# 0_CONNECTOR.net
KiCad netlist of a schematic drawn in Altium Designer
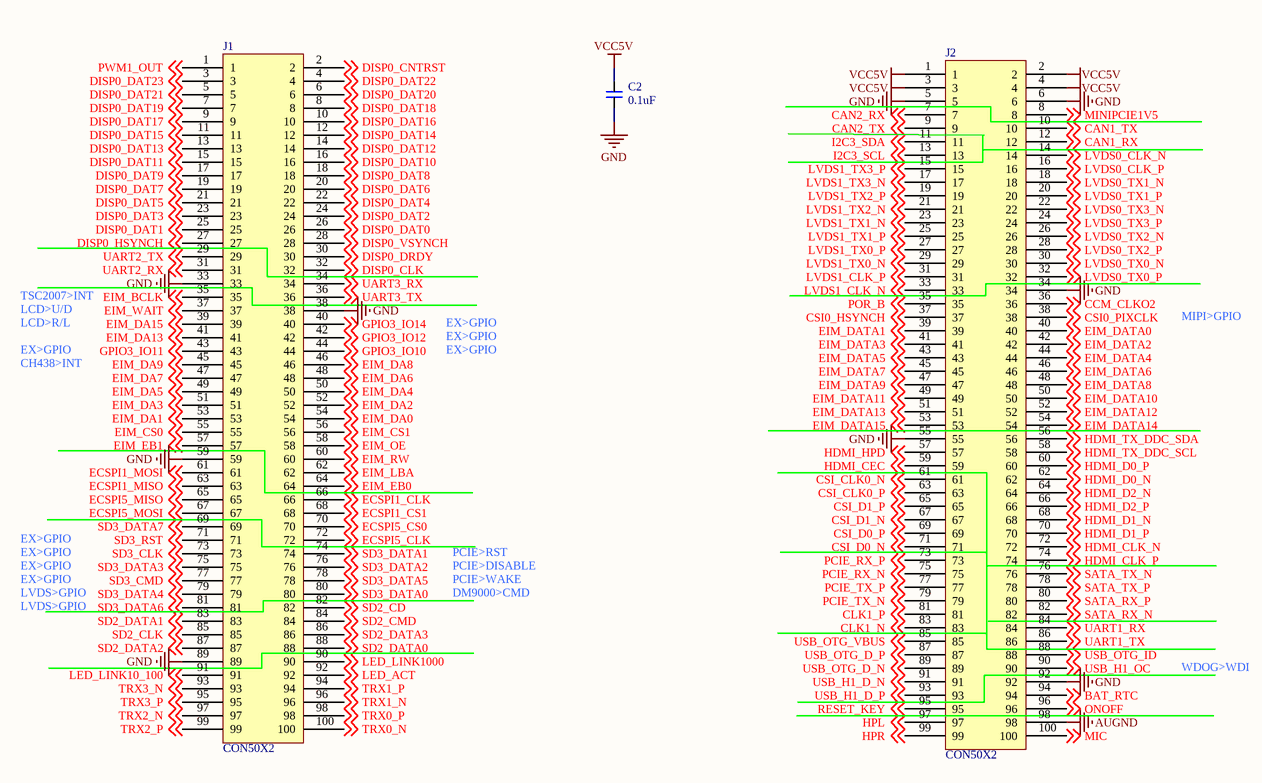
[diagram p0: 0.CONNECTOR.SchDoc]

(export (version "E")
  (design (tool "Eeschema 10.0.6"))
  (components
    (comp (ref "C2")
      (value "0.1uF")
      (footprint "0603C")
      (description "电容")
      (libsource (lib "LDT-SCH") (part "电容"))
    )
    (comp (ref "J1")
      (value "CON50X2")
      (footprint "IDC50X2-1.27MM_SMT")
      (description "ASTRON B2B Connector")
      (libsource (lib "LDT-SCH") (part "CON50X2"))
    )
    (comp (ref "J2")
      (value "CON50X2")
      (footprint "IDC50X2-1.27MM_SMT")
      (description "ASTRON B2B Connector")
      (libsource (lib "LDT-SCH") (part "CON50X2"))
    )
  )
  (nets
    (net (code "1") (name "AUGND") (class "Default")
      (node (ref "J2") (pin "98") (pinfunction "98_98") (pintype "passive"))
    )
    (net (code "2") (name "BAT_RTC") (class "Default")
      (node (ref "J2") (pin "94") (pinfunction "94_94") (pintype "passive"))
    )
    (net (code "3") (name "CAN1_RX") (class "Default")
      (node (ref "J2") (pin "12") (pinfunction "12_12") (pintype "passive"))
    )
    (net (code "4") (name "CAN1_TX") (class "Default")
      (node (ref "J2") (pin "10") (pinfunction "10_10") (pintype "passive"))
    )
    (net (code "5") (name "CAN2_RX") (class "Default")
      (node (ref "J2") (pin "7") (pinfunction "7_7") (pintype "passive"))
    )
    (net (code "6") (name "CAN2_TX") (class "Default")
      (node (ref "J2") (pin "9") (pinfunction "9_9") (pintype "passive"))
    )
    (net (code "7") (name "CCM_CLKO2") (class "Default")
      (node (ref "J2") (pin "36") (pinfunction "36_36") (pintype "passive"))
    )
    (net (code "8") (name "CLK1_N") (class "Default")
      (node (ref "J2") (pin "83") (pinfunction "83_83") (pintype "passive"))
    )
    (net (code "9") (name "CLK1_P") (class "Default")
      (node (ref "J2") (pin "81") (pinfunction "81_81") (pintype "passive"))
    )
    (net (code "10") (name "CSI0_HSYNCH") (class "Default")
      (node (ref "J2") (pin "37") (pinfunction "37_37") (pintype "passive"))
    )
    (net (code "11") (name "CSI0_PIXCLK") (class "Default")
      (node (ref "J2") (pin "38") (pinfunction "38_38") (pintype "passive"))
    )
    (net (code "12") (name "CSI_CLK0_N") (class "Default")
      (node (ref "J2") (pin "61") (pinfunction "61_61") (pintype "passive"))
    )
    (net (code "13") (name "CSI_CLK0_P") (class "Default")
      (node (ref "J2") (pin "63") (pinfunction "63_63") (pintype "passive"))
    )
    (net (code "14") (name "CSI_D0_N") (class "Default")
      (node (ref "J2") (pin "71") (pinfunction "71_71") (pintype "passive"))
    )
    (net (code "15") (name "CSI_D0_P") (class "Default")
      (node (ref "J2") (pin "69") (pinfunction "69_69") (pintype "passive"))
    )
    (net (code "16") (name "CSI_D1_N") (class "Default")
      (node (ref "J2") (pin "67") (pinfunction "67_67") (pintype "passive"))
    )
    (net (code "17") (name "CSI_D1_P") (class "Default")
      (node (ref "J2") (pin "65") (pinfunction "65_65") (pintype "passive"))
    )
    (net (code "18") (name "DISP0_CLK") (class "Default")
      (node (ref "J1") (pin "32") (pinfunction "32_32") (pintype "passive"))
    )
    (net (code "19") (name "DISP0_CNTRST") (class "Default")
      (node (ref "J1") (pin "2") (pinfunction "2_2") (pintype "passive"))
    )
    (net (code "20") (name "DISP0_DAT0") (class "Default")
      (node (ref "J1") (pin "26") (pinfunction "26_26") (pintype "passive"))
    )
    (net (code "21") (name "DISP0_DAT1") (class "Default")
      (node (ref "J1") (pin "25") (pinfunction "25_25") (pintype "passive"))
    )
    (net (code "22") (name "DISP0_DAT2") (class "Default")
      (node (ref "J1") (pin "24") (pinfunction "24_24") (pintype "passive"))
    )
    (net (code "23") (name "DISP0_DAT3") (class "Default")
      (node (ref "J1") (pin "23") (pinfunction "23_23") (pintype "passive"))
    )
    (net (code "24") (name "DISP0_DAT4") (class "Default")
      (node (ref "J1") (pin "22") (pinfunction "22_22") (pintype "passive"))
    )
    (net (code "25") (name "DISP0_DAT5") (class "Default")
      (node (ref "J1") (pin "21") (pinfunction "21_21") (pintype "passive"))
    )
    (net (code "26") (name "DISP0_DAT6") (class "Default")
      (node (ref "J1") (pin "20") (pinfunction "20_20") (pintype "passive"))
    )
    (net (code "27") (name "DISP0_DAT7") (class "Default")
      (node (ref "J1") (pin "19") (pinfunction "19_19") (pintype "passive"))
    )
    (net (code "28") (name "DISP0_DAT8") (class "Default")
      (node (ref "J1") (pin "18") (pinfunction "18_18") (pintype "passive"))
    )
    (net (code "29") (name "DISP0_DAT9") (class "Default")
      (node (ref "J1") (pin "17") (pinfunction "17_17") (pintype "passive"))
    )
    (net (code "30") (name "DISP0_DAT10") (class "Default")
      (node (ref "J1") (pin "16") (pinfunction "16_16") (pintype "passive"))
    )
    (net (code "31") (name "DISP0_DAT11") (class "Default")
      (node (ref "J1") (pin "15") (pinfunction "15_15") (pintype "passive"))
    )
    (net (code "32") (name "DISP0_DAT12") (class "Default")
      (node (ref "J1") (pin "14") (pinfunction "14_14") (pintype "passive"))
    )
    (net (code "33") (name "DISP0_DAT13") (class "Default")
      (node (ref "J1") (pin "13") (pinfunction "13_13") (pintype "passive"))
    )
    (net (code "34") (name "DISP0_DAT14") (class "Default")
      (node (ref "J1") (pin "12") (pinfunction "12_12") (pintype "passive"))
    )
    (net (code "35") (name "DISP0_DAT15") (class "Default")
      (node (ref "J1") (pin "11") (pinfunction "11_11") (pintype "passive"))
    )
    (net (code "36") (name "DISP0_DAT16") (class "Default")
      (node (ref "J1") (pin "10") (pinfunction "10_10") (pintype "passive"))
    )
    (net (code "37") (name "DISP0_DAT17") (class "Default")
      (node (ref "J1") (pin "9") (pinfunction "9_9") (pintype "passive"))
    )
    (net (code "38") (name "DISP0_DAT18") (class "Default")
      (node (ref "J1") (pin "8") (pinfunction "8_8") (pintype "passive"))
    )
    (net (code "39") (name "DISP0_DAT19") (class "Default")
      (node (ref "J1") (pin "7") (pinfunction "7_7") (pintype "passive"))
    )
    (net (code "40") (name "DISP0_DAT20") (class "Default")
      (node (ref "J1") (pin "6") (pinfunction "6_6") (pintype "passive"))
    )
    (net (code "41") (name "DISP0_DAT21") (class "Default")
      (node (ref "J1") (pin "5") (pinfunction "5_5") (pintype "passive"))
    )
    (net (code "42") (name "DISP0_DAT22") (class "Default")
      (node (ref "J1") (pin "4") (pinfunction "4_4") (pintype "passive"))
    )
    (net (code "43") (name "DISP0_DAT23") (class "Default")
      (node (ref "J1") (pin "3") (pinfunction "3_3") (pintype "passive"))
    )
    (net (code "44") (name "DISP0_DRDY") (class "Default")
      (node (ref "J1") (pin "30") (pinfunction "30_30") (pintype "passive"))
    )
    (net (code "45") (name "DISP0_HSYNCH") (class "Default")
      (node (ref "J1") (pin "27") (pinfunction "27_27") (pintype "passive"))
    )
    (net (code "46") (name "DISP0_VSYNCH") (class "Default")
      (node (ref "J1") (pin "28") (pinfunction "28_28") (pintype "passive"))
    )
    (net (code "47") (name "ECSPI1_CLK") (class "Default")
      (node (ref "J1") (pin "66") (pinfunction "66_66") (pintype "passive"))
    )
    (net (code "48") (name "ECSPI1_CS1") (class "Default")
      (node (ref "J1") (pin "68") (pinfunction "68_68") (pintype "passive"))
    )
    (net (code "49") (name "ECSPI1_MISO") (class "Default")
      (node (ref "J1") (pin "63") (pinfunction "63_63") (pintype "passive"))
    )
    (net (code "50") (name "ECSPI1_MOSI") (class "Default")
      (node (ref "J1") (pin "61") (pinfunction "61_61") (pintype "passive"))
    )
    (net (code "51") (name "ECSPI5_CLK") (class "Default")
      (node (ref "J1") (pin "72") (pinfunction "72_72") (pintype "passive"))
    )
    (net (code "52") (name "ECSPI5_CS0") (class "Default")
      (node (ref "J1") (pin "70") (pinfunction "70_70") (pintype "passive"))
    )
    (net (code "53") (name "ECSPI5_MISO") (class "Default")
      (node (ref "J1") (pin "65") (pinfunction "65_65") (pintype "passive"))
    )
    (net (code "54") (name "ECSPI5_MOSI") (class "Default")
      (node (ref "J1") (pin "67") (pinfunction "67_67") (pintype "passive"))
    )
    (net (code "55") (name "EIM_BCLK") (class "Default")
      (node (ref "J1") (pin "35") (pinfunction "35_35") (pintype "passive"))
    )
    (net (code "56") (name "EIM_CS0") (class "Default")
      (node (ref "J1") (pin "55") (pinfunction "55_55") (pintype "passive"))
    )
    (net (code "57") (name "EIM_CS1") (class "Default")
      (node (ref "J1") (pin "56") (pinfunction "56_56") (pintype "passive"))
    )
    (net (code "58") (name "EIM_DA0") (class "Default")
      (node (ref "J1") (pin "54") (pinfunction "54_54") (pintype "passive"))
    )
    (net (code "59") (name "EIM_DA1") (class "Default")
      (node (ref "J1") (pin "53") (pinfunction "53_53") (pintype "passive"))
    )
    (net (code "60") (name "EIM_DA2") (class "Default")
      (node (ref "J1") (pin "52") (pinfunction "52_52") (pintype "passive"))
    )
    (net (code "61") (name "EIM_DA3") (class "Default")
      (node (ref "J1") (pin "51") (pinfunction "51_51") (pintype "passive"))
    )
    (net (code "62") (name "EIM_DA4") (class "Default")
      (node (ref "J1") (pin "50") (pinfunction "50_50") (pintype "passive"))
    )
    (net (code "63") (name "EIM_DA5") (class "Default")
      (node (ref "J1") (pin "49") (pinfunction "49_49") (pintype "passive"))
    )
    (net (code "64") (name "EIM_DA6") (class "Default")
      (node (ref "J1") (pin "48") (pinfunction "48_48") (pintype "passive"))
    )
    (net (code "65") (name "EIM_DA7") (class "Default")
      (node (ref "J1") (pin "47") (pinfunction "47_47") (pintype "passive"))
    )
    (net (code "66") (name "EIM_DA8") (class "Default")
      (node (ref "J1") (pin "46") (pinfunction "46_46") (pintype "passive"))
    )
    (net (code "67") (name "EIM_DA9") (class "Default")
      (node (ref "J1") (pin "45") (pinfunction "45_45") (pintype "passive"))
    )
    (net (code "68") (name "EIM_DA13") (class "Default")
      (node (ref "J1") (pin "41") (pinfunction "41_41") (pintype "passive"))
    )
    (net (code "69") (name "EIM_DA15") (class "Default")
      (node (ref "J1") (pin "39") (pinfunction "39_39") (pintype "passive"))
    )
    (net (code "70") (name "EIM_DATA0") (class "Default")
      (node (ref "J2") (pin "40") (pinfunction "40_40") (pintype "passive"))
    )
    (net (code "71") (name "EIM_DATA1") (class "Default")
      (node (ref "J2") (pin "39") (pinfunction "39_39") (pintype "passive"))
    )
    (net (code "72") (name "EIM_DATA2") (class "Default")
      (node (ref "J2") (pin "42") (pinfunction "42_42") (pintype "passive"))
    )
    (net (code "73") (name "EIM_DATA3") (class "Default")
      (node (ref "J2") (pin "41") (pinfunction "41_41") (pintype "passive"))
    )
    (net (code "74") (name "EIM_DATA4") (class "Default")
      (node (ref "J2") (pin "44") (pinfunction "44_44") (pintype "passive"))
    )
    (net (code "75") (name "EIM_DATA5") (class "Default")
      (node (ref "J2") (pin "43") (pinfunction "43_43") (pintype "passive"))
    )
    (net (code "76") (name "EIM_DATA6") (class "Default")
      (node (ref "J2") (pin "46") (pinfunction "46_46") (pintype "passive"))
    )
    (net (code "77") (name "EIM_DATA7") (class "Default")
      (node (ref "J2") (pin "45") (pinfunction "45_45") (pintype "passive"))
    )
    (net (code "78") (name "EIM_DATA8") (class "Default")
      (node (ref "J2") (pin "48") (pinfunction "48_48") (pintype "passive"))
    )
    (net (code "79") (name "EIM_DATA9") (class "Default")
      (node (ref "J2") (pin "47") (pinfunction "47_47") (pintype "passive"))
    )
    (net (code "80") (name "EIM_DATA10") (class "Default")
      (node (ref "J2") (pin "50") (pinfunction "50_50") (pintype "passive"))
    )
    (net (code "81") (name "EIM_DATA11") (class "Default")
      (node (ref "J2") (pin "49") (pinfunction "49_49") (pintype "passive"))
    )
    (net (code "82") (name "EIM_DATA12") (class "Default")
      (node (ref "J2") (pin "52") (pinfunction "52_52") (pintype "passive"))
    )
    (net (code "83") (name "EIM_DATA13") (class "Default")
      (node (ref "J2") (pin "51") (pinfunction "51_51") (pintype "passive"))
    )
    (net (code "84") (name "EIM_DATA14") (class "Default")
      (node (ref "J2") (pin "54") (pinfunction "54_54") (pintype "passive"))
    )
    (net (code "85") (name "EIM_DATA15") (class "Default")
      (node (ref "J2") (pin "53") (pinfunction "53_53") (pintype "passive"))
    )
    (net (code "86") (name "EIM_EB0") (class "Default")
      (node (ref "J1") (pin "64") (pinfunction "64_64") (pintype "passive"))
    )
    (net (code "87") (name "EIM_EB1") (class "Default")
      (node (ref "J1") (pin "57") (pinfunction "57_57") (pintype "passive"))
    )
    (net (code "88") (name "EIM_LBA") (class "Default")
      (node (ref "J1") (pin "62") (pinfunction "62_62") (pintype "passive"))
    )
    (net (code "89") (name "EIM_OE") (class "Default")
      (node (ref "J1") (pin "58") (pinfunction "58_58") (pintype "passive"))
    )
    (net (code "90") (name "EIM_RW") (class "Default")
      (node (ref "J1") (pin "60") (pinfunction "60_60") (pintype "passive"))
    )
    (net (code "91") (name "EIM_WAIT") (class "Default")
      (node (ref "J1") (pin "37") (pinfunction "37_37") (pintype "passive"))
    )
    (net (code "92") (name "GND") (class "Default")
      (node (ref "C2") (pin "2") (pintype "passive"))
      (node (ref "J1") (pin "33") (pinfunction "33_33") (pintype "passive"))
      (node (ref "J1") (pin "38") (pinfunction "38_38") (pintype "passive"))
      (node (ref "J1") (pin "59") (pinfunction "59_59") (pintype "passive"))
      (node (ref "J1") (pin "89") (pinfunction "89_89") (pintype "passive"))
      (node (ref "J2") (pin "34") (pinfunction "34_34") (pintype "passive"))
      (node (ref "J2") (pin "5") (pinfunction "5_5") (pintype "passive"))
      (node (ref "J2") (pin "55") (pinfunction "55_55") (pintype "passive"))
      (node (ref "J2") (pin "6") (pinfunction "6_6") (pintype "passive"))
      (node (ref "J2") (pin "92") (pinfunction "92_92") (pintype "passive"))
    )
    (net (code "93") (name "GPIO3_IO10") (class "Default")
      (node (ref "J1") (pin "44") (pinfunction "44_44") (pintype "passive"))
    )
    (net (code "94") (name "GPIO3_IO11") (class "Default")
      (node (ref "J1") (pin "43") (pinfunction "43_43") (pintype "passive"))
    )
    (net (code "95") (name "GPIO3_IO12") (class "Default")
      (node (ref "J1") (pin "42") (pinfunction "42_42") (pintype "passive"))
    )
    (net (code "96") (name "GPIO3_IO14") (class "Default")
      (node (ref "J1") (pin "40") (pinfunction "40_40") (pintype "passive"))
    )
    (net (code "97") (name "HDMI_CEC") (class "Default")
      (node (ref "J2") (pin "59") (pinfunction "59_59") (pintype "passive"))
    )
    (net (code "98") (name "HDMI_CLK_N") (class "Default")
      (node (ref "J2") (pin "72") (pinfunction "72_72") (pintype "passive"))
    )
    (net (code "99") (name "HDMI_CLK_P") (class "Default")
      (node (ref "J2") (pin "74") (pinfunction "74_74") (pintype "passive"))
    )
    (net (code "100") (name "HDMI_D0_N") (class "Default")
      (node (ref "J2") (pin "62") (pinfunction "62_62") (pintype "passive"))
    )
    (net (code "101") (name "HDMI_D0_P") (class "Default")
      (node (ref "J2") (pin "60") (pinfunction "60_60") (pintype "passive"))
    )
    (net (code "102") (name "HDMI_D1_N") (class "Default")
      (node (ref "J2") (pin "68") (pinfunction "68_68") (pintype "passive"))
    )
    (net (code "103") (name "HDMI_D1_P") (class "Default")
      (node (ref "J2") (pin "70") (pinfunction "70_70") (pintype "passive"))
    )
    (net (code "104") (name "HDMI_D2_N") (class "Default")
      (node (ref "J2") (pin "64") (pinfunction "64_64") (pintype "passive"))
    )
    (net (code "105") (name "HDMI_D2_P") (class "Default")
      (node (ref "J2") (pin "66") (pinfunction "66_66") (pintype "passive"))
    )
    (net (code "106") (name "HDMI_HPD") (class "Default")
      (node (ref "J2") (pin "57") (pinfunction "57_57") (pintype "passive"))
    )
    (net (code "107") (name "HDMI_TX_DDC_SCL") (class "Default")
      (node (ref "J2") (pin "58") (pinfunction "58_58") (pintype "passive"))
    )
    (net (code "108") (name "HDMI_TX_DDC_SDA") (class "Default")
      (node (ref "J2") (pin "56") (pinfunction "56_56") (pintype "passive"))
    )
    (net (code "109") (name "HPL") (class "Default")
      (node (ref "J2") (pin "97") (pinfunction "97_97") (pintype "passive"))
    )
    (net (code "110") (name "HPR") (class "Default")
      (node (ref "J2") (pin "99") (pinfunction "99_99") (pintype "passive"))
    )
    (net (code "111") (name "I2C3_SCL") (class "Default")
      (node (ref "J2") (pin "13") (pinfunction "13_13") (pintype "passive"))
    )
    (net (code "112") (name "I2C3_SDA") (class "Default")
      (node (ref "J2") (pin "11") (pinfunction "11_11") (pintype "passive"))
    )
    (net (code "113") (name "LED_ACT") (class "Default")
      (node (ref "J1") (pin "92") (pinfunction "92_92") (pintype "passive"))
    )
    (net (code "114") (name "LED_LINK10_100") (class "Default")
      (node (ref "J1") (pin "91") (pinfunction "91_91") (pintype "passive"))
    )
    (net (code "115") (name "LED_LINK1000") (class "Default")
      (node (ref "J1") (pin "90") (pinfunction "90_90") (pintype "passive"))
    )
    (net (code "116") (name "LVDS0_CLK_N") (class "Default")
      (node (ref "J2") (pin "14") (pinfunction "14_14") (pintype "passive"))
    )
    (net (code "117") (name "LVDS0_CLK_P") (class "Default")
      (node (ref "J2") (pin "16") (pinfunction "16_16") (pintype "passive"))
    )
    (net (code "118") (name "LVDS0_TX0_N") (class "Default")
      (node (ref "J2") (pin "30") (pinfunction "30_30") (pintype "passive"))
    )
    (net (code "119") (name "LVDS0_TX0_P") (class "Default")
      (node (ref "J2") (pin "32") (pinfunction "32_32") (pintype "passive"))
    )
    (net (code "120") (name "LVDS0_TX1_N") (class "Default")
      (node (ref "J2") (pin "18") (pinfunction "18_18") (pintype "passive"))
    )
    (net (code "121") (name "LVDS0_TX1_P") (class "Default")
      (node (ref "J2") (pin "20") (pinfunction "20_20") (pintype "passive"))
    )
    (net (code "122") (name "LVDS0_TX2_N") (class "Default")
      (node (ref "J2") (pin "26") (pinfunction "26_26") (pintype "passive"))
    )
    (net (code "123") (name "LVDS0_TX2_P") (class "Default")
      (node (ref "J2") (pin "28") (pinfunction "28_28") (pintype "passive"))
    )
    (net (code "124") (name "LVDS0_TX3_N") (class "Default")
      (node (ref "J2") (pin "22") (pinfunction "22_22") (pintype "passive"))
    )
    (net (code "125") (name "LVDS0_TX3_P") (class "Default")
      (node (ref "J2") (pin "24") (pinfunction "24_24") (pintype "passive"))
    )
    (net (code "126") (name "LVDS1_CLK_N") (class "Default")
      (node (ref "J2") (pin "33") (pinfunction "33_33") (pintype "passive"))
    )
    (net (code "127") (name "LVDS1_CLK_P") (class "Default")
      (node (ref "J2") (pin "31") (pinfunction "31_31") (pintype "passive"))
    )
    (net (code "128") (name "LVDS1_TX0_N") (class "Default")
      (node (ref "J2") (pin "29") (pinfunction "29_29") (pintype "passive"))
    )
    (net (code "129") (name "LVDS1_TX0_P") (class "Default")
      (node (ref "J2") (pin "27") (pinfunction "27_27") (pintype "passive"))
    )
    (net (code "130") (name "LVDS1_TX1_N") (class "Default")
      (node (ref "J2") (pin "23") (pinfunction "23_23") (pintype "passive"))
    )
    (net (code "131") (name "LVDS1_TX1_P") (class "Default")
      (node (ref "J2") (pin "25") (pinfunction "25_25") (pintype "passive"))
    )
    (net (code "132") (name "LVDS1_TX2_N") (class "Default")
      (node (ref "J2") (pin "21") (pinfunction "21_21") (pintype "passive"))
    )
    (net (code "133") (name "LVDS1_TX2_P") (class "Default")
      (node (ref "J2") (pin "19") (pinfunction "19_19") (pintype "passive"))
    )
    (net (code "134") (name "LVDS1_TX3_N") (class "Default")
      (node (ref "J2") (pin "17") (pinfunction "17_17") (pintype "passive"))
    )
    (net (code "135") (name "LVDS1_TX3_P") (class "Default")
      (node (ref "J2") (pin "15") (pinfunction "15_15") (pintype "passive"))
    )
    (net (code "136") (name "MIC") (class "Default")
      (node (ref "J2") (pin "100") (pinfunction "100_100") (pintype "passive"))
    )
    (net (code "137") (name "MINIPCIE1V5") (class "Default")
      (node (ref "J2") (pin "8") (pinfunction "8_8") (pintype "passive"))
    )
    (net (code "138") (name "ONOFF") (class "Default")
      (node (ref "J2") (pin "96") (pinfunction "96_96") (pintype "passive"))
    )
    (net (code "139") (name "PCIE_RX_N") (class "Default")
      (node (ref "J2") (pin "75") (pinfunction "75_75") (pintype "passive"))
    )
    (net (code "140") (name "PCIE_RX_P") (class "Default")
      (node (ref "J2") (pin "73") (pinfunction "73_73") (pintype "passive"))
    )
    (net (code "141") (name "PCIE_TX_N") (class "Default")
      (node (ref "J2") (pin "79") (pinfunction "79_79") (pintype "passive"))
    )
    (net (code "142") (name "PCIE_TX_P") (class "Default")
      (node (ref "J2") (pin "77") (pinfunction "77_77") (pintype "passive"))
    )
    (net (code "143") (name "POR_B") (class "Default")
      (node (ref "J2") (pin "35") (pinfunction "35_35") (pintype "passive"))
    )
    (net (code "144") (name "PWM1_OUT") (class "Default")
      (node (ref "J1") (pin "1") (pinfunction "1_1") (pintype "passive"))
    )
    (net (code "145") (name "RESET_KEY") (class "Default")
      (node (ref "J2") (pin "95") (pinfunction "95_95") (pintype "passive"))
    )
    (net (code "146") (name "SATA_RX_N") (class "Default")
      (node (ref "J2") (pin "82") (pinfunction "82_82") (pintype "passive"))
    )
    (net (code "147") (name "SATA_RX_P") (class "Default")
      (node (ref "J2") (pin "80") (pinfunction "80_80") (pintype "passive"))
    )
    (net (code "148") (name "SATA_TX_N") (class "Default")
      (node (ref "J2") (pin "76") (pinfunction "76_76") (pintype "passive"))
    )
    (net (code "149") (name "SATA_TX_P") (class "Default")
      (node (ref "J2") (pin "78") (pinfunction "78_78") (pintype "passive"))
    )
    (net (code "150") (name "SD2_CD") (class "Default")
      (node (ref "J1") (pin "82") (pinfunction "82_82") (pintype "passive"))
    )
    (net (code "151") (name "SD2_CLK") (class "Default")
      (node (ref "J1") (pin "85") (pinfunction "85_85") (pintype "passive"))
    )
    (net (code "152") (name "SD2_CMD") (class "Default")
      (node (ref "J1") (pin "84") (pinfunction "84_84") (pintype "passive"))
    )
    (net (code "153") (name "SD2_DATA0") (class "Default")
      (node (ref "J1") (pin "88") (pinfunction "88_88") (pintype "passive"))
    )
    (net (code "154") (name "SD2_DATA1") (class "Default")
      (node (ref "J1") (pin "83") (pinfunction "83_83") (pintype "passive"))
    )
    (net (code "155") (name "SD2_DATA2") (class "Default")
      (node (ref "J1") (pin "87") (pinfunction "87_87") (pintype "passive"))
    )
    (net (code "156") (name "SD2_DATA3") (class "Default")
      (node (ref "J1") (pin "86") (pinfunction "86_86") (pintype "passive"))
    )
    (net (code "157") (name "SD3_CLK") (class "Default")
      (node (ref "J1") (pin "73") (pinfunction "73_73") (pintype "passive"))
    )
    (net (code "158") (name "SD3_CMD") (class "Default")
      (node (ref "J1") (pin "77") (pinfunction "77_77") (pintype "passive"))
    )
    (net (code "159") (name "SD3_DATA0") (class "Default")
      (node (ref "J1") (pin "80") (pinfunction "80_80") (pintype "passive"))
    )
    (net (code "160") (name "SD3_DATA1") (class "Default")
      (node (ref "J1") (pin "74") (pinfunction "74_74") (pintype "passive"))
    )
    (net (code "161") (name "SD3_DATA2") (class "Default")
      (node (ref "J1") (pin "76") (pinfunction "76_76") (pintype "passive"))
    )
    (net (code "162") (name "SD3_DATA3") (class "Default")
      (node (ref "J1") (pin "75") (pinfunction "75_75") (pintype "passive"))
    )
    (net (code "163") (name "SD3_DATA4") (class "Default")
      (node (ref "J1") (pin "79") (pinfunction "79_79") (pintype "passive"))
    )
    (net (code "164") (name "SD3_DATA5") (class "Default")
      (node (ref "J1") (pin "78") (pinfunction "78_78") (pintype "passive"))
    )
    (net (code "165") (name "SD3_DATA6") (class "Default")
      (node (ref "J1") (pin "81") (pinfunction "81_81") (pintype "passive"))
    )
    (net (code "166") (name "SD3_DATA7") (class "Default")
      (node (ref "J1") (pin "69") (pinfunction "69_69") (pintype "passive"))
    )
    (net (code "167") (name "SD3_RST") (class "Default")
      (node (ref "J1") (pin "71") (pinfunction "71_71") (pintype "passive"))
    )
    (net (code "168") (name "TRX0_N") (class "Default")
      (node (ref "J1") (pin "100") (pinfunction "100_100") (pintype "passive"))
    )
    (net (code "169") (name "TRX0_P") (class "Default")
      (node (ref "J1") (pin "98") (pinfunction "98_98") (pintype "passive"))
    )
    (net (code "170") (name "TRX1_N") (class "Default")
      (node (ref "J1") (pin "96") (pinfunction "96_96") (pintype "passive"))
    )
    (net (code "171") (name "TRX1_P") (class "Default")
      (node (ref "J1") (pin "94") (pinfunction "94_94") (pintype "passive"))
    )
    (net (code "172") (name "TRX2_N") (class "Default")
      (node (ref "J1") (pin "97") (pinfunction "97_97") (pintype "passive"))
    )
    (net (code "173") (name "TRX2_P") (class "Default")
      (node (ref "J1") (pin "99") (pinfunction "99_99") (pintype "passive"))
    )
    (net (code "174") (name "TRX3_N") (class "Default")
      (node (ref "J1") (pin "93") (pinfunction "93_93") (pintype "passive"))
    )
    (net (code "175") (name "TRX3_P") (class "Default")
      (node (ref "J1") (pin "95") (pinfunction "95_95") (pintype "passive"))
    )
    (net (code "176") (name "UART1_RX") (class "Default")
      (node (ref "J2") (pin "84") (pinfunction "84_84") (pintype "passive"))
    )
    (net (code "177") (name "UART1_TX") (class "Default")
      (node (ref "J2") (pin "86") (pinfunction "86_86") (pintype "passive"))
    )
    (net (code "178") (name "UART2_RX") (class "Default")
      (node (ref "J1") (pin "31") (pinfunction "31_31") (pintype "passive"))
    )
    (net (code "179") (name "UART2_TX") (class "Default")
      (node (ref "J1") (pin "29") (pinfunction "29_29") (pintype "passive"))
    )
    (net (code "180") (name "UART3_RX") (class "Default")
      (node (ref "J1") (pin "34") (pinfunction "34_34") (pintype "passive"))
    )
    (net (code "181") (name "UART3_TX") (class "Default")
      (node (ref "J1") (pin "36") (pinfunction "36_36") (pintype "passive"))
    )
    (net (code "182") (name "USB_H1_D_N") (class "Default")
      (node (ref "J2") (pin "91") (pinfunction "91_91") (pintype "passive"))
    )
    (net (code "183") (name "USB_H1_D_P") (class "Default")
      (node (ref "J2") (pin "93") (pinfunction "93_93") (pintype "passive"))
    )
    (net (code "184") (name "USB_H1_OC") (class "Default")
      (node (ref "J2") (pin "90") (pinfunction "90_90") (pintype "passive"))
    )
    (net (code "185") (name "USB_OTG_D_N") (class "Default")
      (node (ref "J2") (pin "89") (pinfunction "89_89") (pintype "passive"))
    )
    (net (code "186") (name "USB_OTG_D_P") (class "Default")
      (node (ref "J2") (pin "87") (pinfunction "87_87") (pintype "passive"))
    )
    (net (code "187") (name "USB_OTG_ID") (class "Default")
      (node (ref "J2") (pin "88") (pinfunction "88_88") (pintype "passive"))
    )
    (net (code "188") (name "USB_OTG_VBUS") (class "Default")
      (node (ref "J2") (pin "85") (pinfunction "85_85") (pintype "passive"))
    )
    (net (code "189") (name "VCC5V") (class "Default")
      (node (ref "C2") (pin "1") (pintype "passive"))
      (node (ref "J2") (pin "1") (pinfunction "1_1") (pintype "passive"))
      (node (ref "J2") (pin "2") (pinfunction "2_2") (pintype "passive"))
      (node (ref "J2") (pin "3") (pinfunction "3_3") (pintype "passive"))
      (node (ref "J2") (pin "4") (pinfunction "4_4") (pintype "passive"))
    )
  )
)
